# Alim-5-12vcc.net
KiCad netlist of a schematic drawn in EAGLE
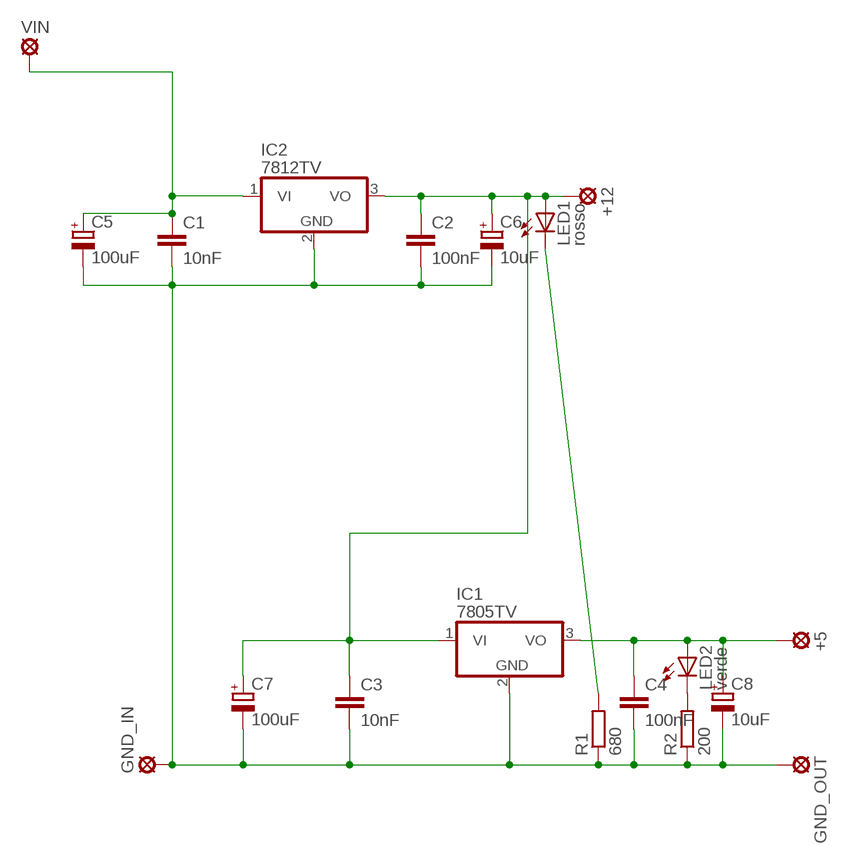
[diagram p0: schematic, sheet 1]

(export (version "E")
  (design (tool "Eeschema 10.0.6"))
  (components
    (comp (ref "+5")
      (value "SE14")
      (footprint "eagle-import:SE14")
      (libsource (lib "eagle-import") (part "SE14"))
    )
    (comp (ref "+12")
      (value "SE14")
      (footprint "eagle-import:SE14")
      (libsource (lib "eagle-import") (part "SE14"))
    )
    (comp (ref "C1")
      (value "10nF")
      (footprint "eagle-import:C050-025X075")
      (libsource (lib "eagle-import") (part "C-EU050-025X075"))
    )
    (comp (ref "C2")
      (value "100nF")
      (footprint "eagle-import:C050-025X075")
      (libsource (lib "eagle-import") (part "C-EU050-025X075"))
    )
    (comp (ref "C3")
      (value "10nF")
      (footprint "eagle-import:C050-025X075")
      (libsource (lib "eagle-import") (part "C-EU050-025X075"))
    )
    (comp (ref "C4")
      (value "100nF")
      (footprint "eagle-import:C050-025X075")
      (libsource (lib "eagle-import") (part "C-EU050-025X075"))
    )
    (comp (ref "C5")
      (value "100uF")
      (footprint "eagle-import:E2,5-6")
      (libsource (lib "eagle-import") (part "CPOL-EUE2.5-6"))
    )
    (comp (ref "C6")
      (value "10uF")
      (footprint "eagle-import:E2,5-6")
      (libsource (lib "eagle-import") (part "CPOL-EUE2.5-6"))
    )
    (comp (ref "C7")
      (value "100uF")
      (footprint "eagle-import:E2,5-6")
      (libsource (lib "eagle-import") (part "CPOL-EUE2.5-6"))
    )
    (comp (ref "C8")
      (value "10uF")
      (footprint "eagle-import:E2,5-6")
      (libsource (lib "eagle-import") (part "CPOL-EUE2.5-6"))
    )
    (comp (ref "GND_IN")
      (value "SE14")
      (footprint "eagle-import:SE14")
      (libsource (lib "eagle-import") (part "SE14"))
    )
    (comp (ref "GND_OUT")
      (value "SE14")
      (footprint "eagle-import:SE14")
      (libsource (lib "eagle-import") (part "SE14"))
    )
    (comp (ref "IC1")
      (value "7805TV")
      (footprint "eagle-import:TO220V")
      (libsource (lib "eagle-import") (part "78TV05"))
    )
    (comp (ref "IC2")
      (value "7812TV")
      (footprint "eagle-import:TO220V")
      (libsource (lib "eagle-import") (part "78TV12"))
    )
    (comp (ref "LED1")
      (value "rosso")
      (footprint "eagle-import:LED5MM")
      (libsource (lib "eagle-import") (part "LED5MM"))
    )
    (comp (ref "LED2")
      (value "verde")
      (footprint "eagle-import:LED5MM")
      (libsource (lib "eagle-import") (part "LED5MM"))
    )
    (comp (ref "R1")
      (value "680")
      (footprint "eagle-import:0204_7")
      (libsource (lib "eagle-import") (part "R-EU_0204/7"))
    )
    (comp (ref "R2")
      (value "200")
      (footprint "eagle-import:0204_7")
      (libsource (lib "eagle-import") (part "R-EU_0204/7"))
    )
    (comp (ref "VIN")
      (value "SE14")
      (footprint "eagle-import:SE14")
      (libsource (lib "eagle-import") (part "SE14"))
    )
  )
  (nets
    (net (code "1") (name "Net-(IC1-GND)") (class "Default")
      (node (ref "C1") (pin "2") (pinfunction "2_2") (pintype "passive"))
      (node (ref "C2") (pin "2") (pinfunction "2_2") (pintype "passive"))
      (node (ref "C3") (pin "2") (pinfunction "2_2") (pintype "passive"))
      (node (ref "C4") (pin "2") (pinfunction "2_2") (pintype "passive"))
      (node (ref "C5") (pin "-") (pinfunction "-_-") (pintype "passive"))
      (node (ref "C6") (pin "-") (pinfunction "-_-") (pintype "passive"))
      (node (ref "C7") (pin "-") (pinfunction "-_-") (pintype "passive"))
      (node (ref "C8") (pin "-") (pinfunction "-_-") (pintype "passive"))
      (node (ref "GND_IN") (pin "MP") (pinfunction "MP_MP") (pintype "passive"))
      (node (ref "GND_OUT") (pin "MP") (pinfunction "MP_MP") (pintype "passive"))
      (node (ref "IC1") (pin "2") (pinfunction "GND_2") (pintype "passive"))
      (node (ref "IC2") (pin "2") (pinfunction "GND_2") (pintype "passive"))
      (node (ref "R1") (pin "1") (pinfunction "1_1") (pintype "passive"))
      (node (ref "R2") (pin "1") (pinfunction "1_1") (pintype "passive"))
    )
    (net (code "2") (name "Net-(IC1-VI)") (class "Default")
      (node (ref "+12") (pin "MP") (pinfunction "MP_MP") (pintype "passive"))
      (node (ref "C2") (pin "1") (pinfunction "1_1") (pintype "passive"))
      (node (ref "C3") (pin "1") (pinfunction "1_1") (pintype "passive"))
      (node (ref "C6") (pin "+") (pinfunction "+_+") (pintype "passive"))
      (node (ref "C7") (pin "+") (pinfunction "+_+") (pintype "passive"))
      (node (ref "IC1") (pin "1") (pinfunction "VI_1") (pintype "input"))
      (node (ref "IC2") (pin "3") (pinfunction "VO_3") (pintype "passive"))
      (node (ref "LED1") (pin "A") (pinfunction "A_A") (pintype "passive"))
    )
    (net (code "3") (name "Net-(IC1-VO)") (class "Default")
      (node (ref "+5") (pin "MP") (pinfunction "MP_MP") (pintype "passive"))
      (node (ref "C4") (pin "1") (pinfunction "1_1") (pintype "passive"))
      (node (ref "C8") (pin "+") (pinfunction "+_+") (pintype "passive"))
      (node (ref "IC1") (pin "3") (pinfunction "VO_3") (pintype "passive"))
      (node (ref "LED2") (pin "A") (pinfunction "A_A") (pintype "passive"))
    )
    (net (code "4") (name "Net-(IC2-VI)") (class "Default")
      (node (ref "C1") (pin "1") (pinfunction "1_1") (pintype "passive"))
      (node (ref "C5") (pin "+") (pinfunction "+_+") (pintype "passive"))
      (node (ref "IC2") (pin "1") (pinfunction "VI_1") (pintype "input"))
      (node (ref "VIN") (pin "MP") (pinfunction "MP_MP") (pintype "passive"))
    )
    (net (code "5") (name "Net-(LED1-C)") (class "Default")
      (node (ref "LED1") (pin "K") (pinfunction "C_K") (pintype "passive"))
      (node (ref "R1") (pin "2") (pinfunction "2_2") (pintype "passive"))
    )
    (net (code "6") (name "Net-(LED2-C)") (class "Default")
      (node (ref "LED2") (pin "K") (pinfunction "C_K") (pintype "passive"))
      (node (ref "R2") (pin "2") (pinfunction "2_2") (pintype "passive"))
    )
  )
)
